# VauTRIOv1_0.net
KiCad netlist of a schematic drawn in EAGLE
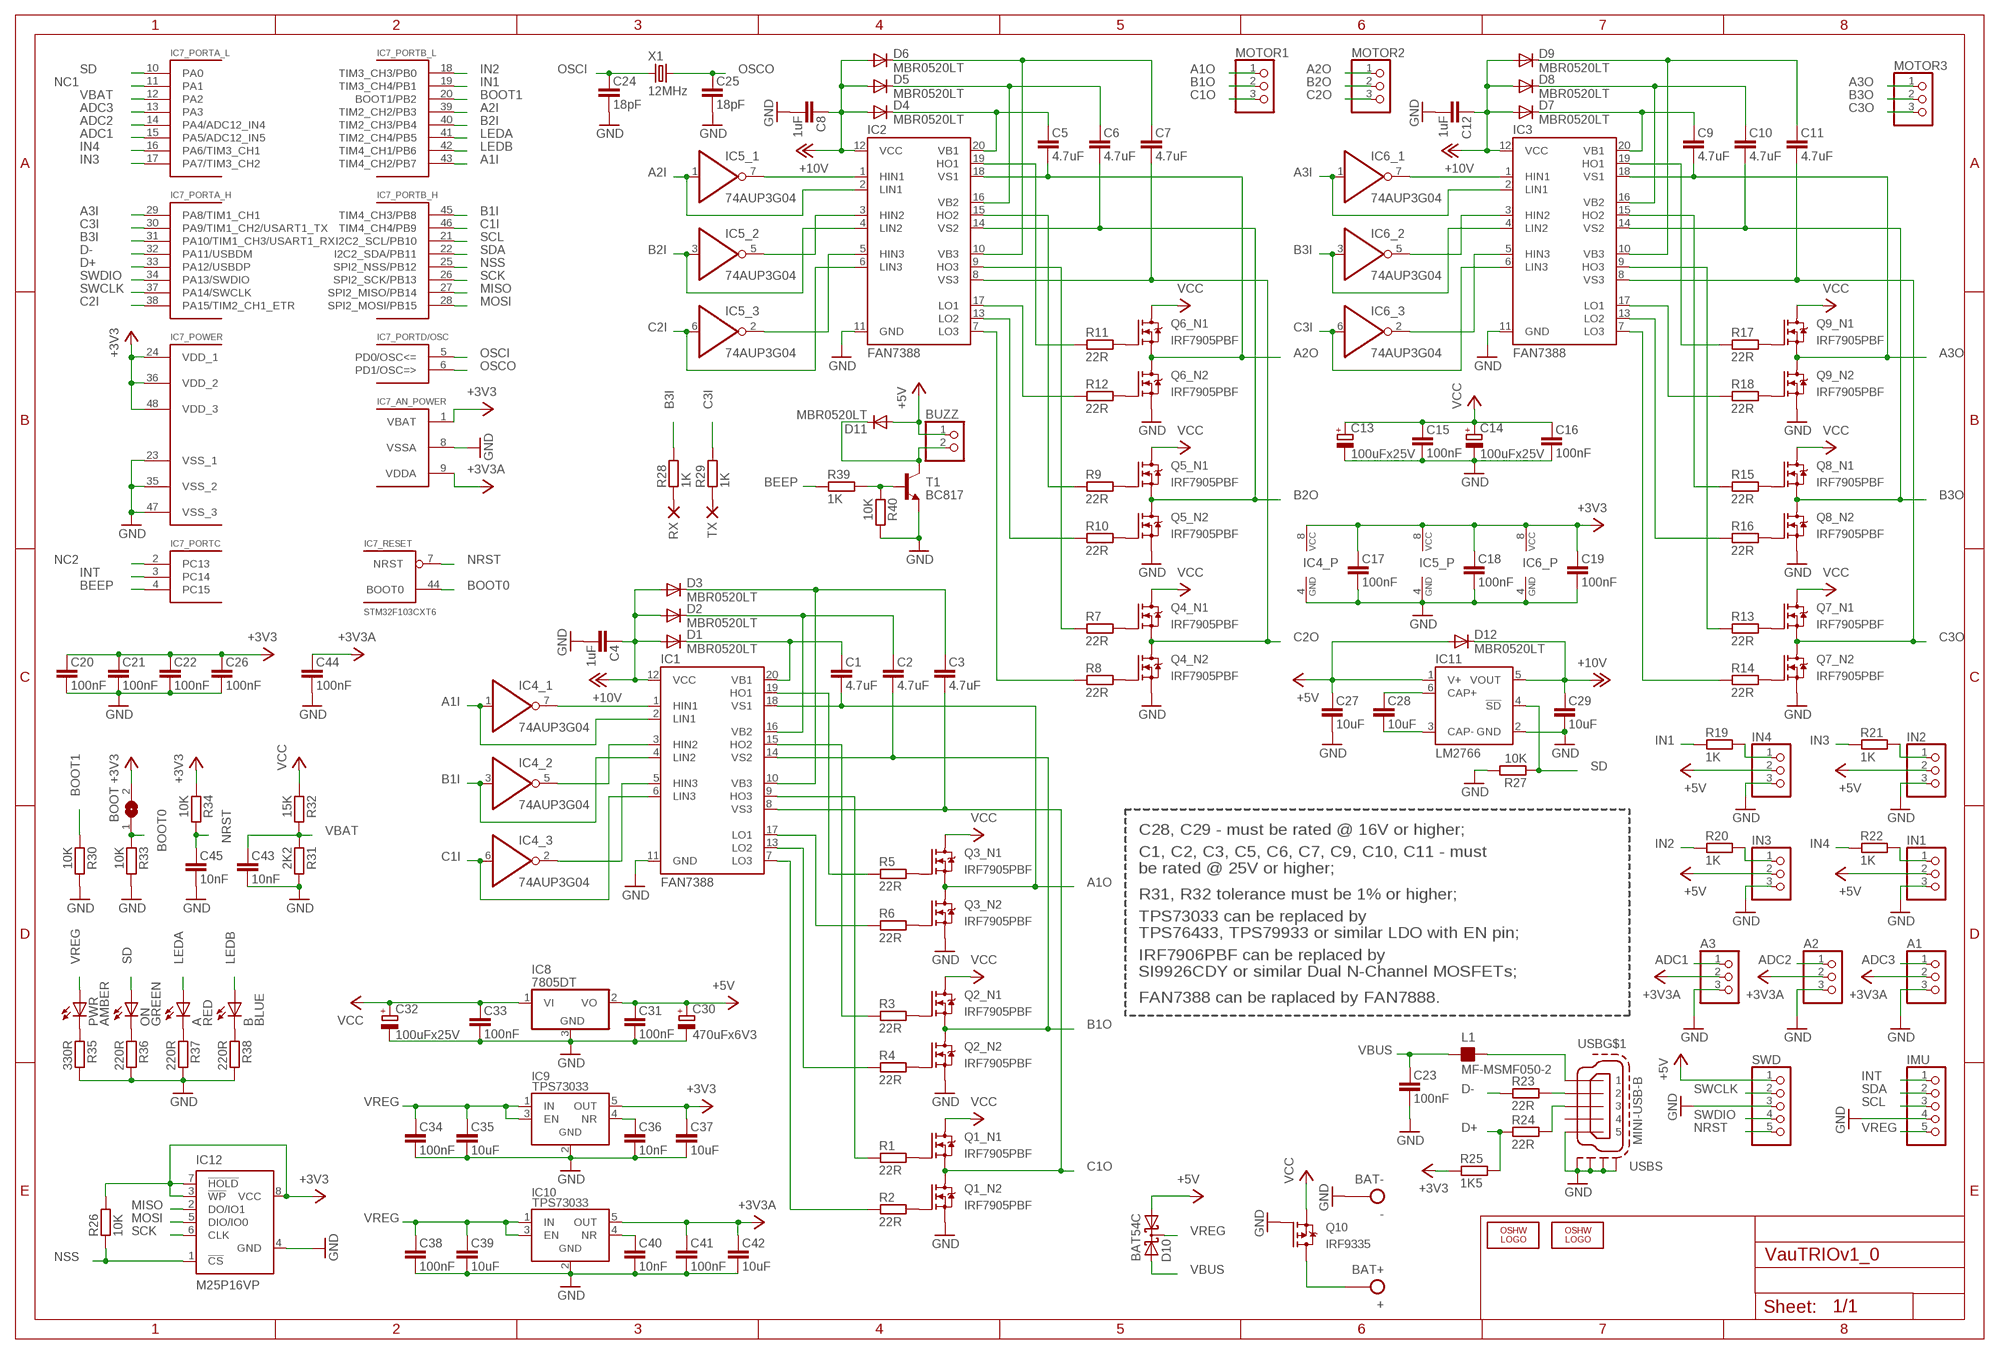
[diagram p0: schematic, sheet 1]

(export (version "E")
  (design (tool "Eeschema 10.0.6"))
  (components
    (comp (ref "+")
      (value "BAT+")
      (footprint "eagle-import:PAD20S")
      (libsource (lib "eagle-import") (part "POWER-PAD-20S"))
    )
    (comp (ref "-")
      (value "BAT-")
      (footprint "eagle-import:PAD20R")
      (libsource (lib "eagle-import") (part "POWER-PAD-20R"))
    )
    (comp (ref "A")
      (value "RED")
      (footprint "eagle-import:CHIPLED_0805")
      (libsource (lib "eagle-import") (part "LEDCHIPLED_0805"))
    )
    (comp (ref "A1")
      (value "PINHD-1X3")
      (footprint "eagle-import:1X03")
      (libsource (lib "eagle-import") (part "PINHD-1X3"))
    )
    (comp (ref "A2")
      (value "PINHD-1X3")
      (footprint "eagle-import:1X03")
      (libsource (lib "eagle-import") (part "PINHD-1X3"))
    )
    (comp (ref "A3")
      (value "PINHD-1X3")
      (footprint "eagle-import:1X03")
      (libsource (lib "eagle-import") (part "PINHD-1X3"))
    )
    (comp (ref "B")
      (value "BLUE")
      (footprint "eagle-import:CHIPLED_0805")
      (libsource (lib "eagle-import") (part "LEDCHIPLED_0805"))
    )
    (comp (ref "BOOT")
      (value "SJ")
      (footprint "eagle-import:SJ")
      (libsource (lib "eagle-import") (part "SJ"))
    )
    (comp (ref "BUZZ")
      (value "PINHD-1X2")
      (footprint "eagle-import:1X02")
      (libsource (lib "eagle-import") (part "PINHD-1X2"))
    )
    (comp (ref "C1")
      (value "4.7uF")
      (footprint "eagle-import:C0805")
      (libsource (lib "eagle-import") (part "C_EU_C0805"))
    )
    (comp (ref "C2")
      (value "4.7uF")
      (footprint "eagle-import:C0805")
      (libsource (lib "eagle-import") (part "C_EU_C0805"))
    )
    (comp (ref "C3")
      (value "4.7uF")
      (footprint "eagle-import:C0805")
      (libsource (lib "eagle-import") (part "C_EU_C0805"))
    )
    (comp (ref "C4")
      (value "1uF")
      (footprint "eagle-import:C0603G")
      (libsource (lib "eagle-import") (part "C_EU_C0603G"))
    )
    (comp (ref "C5")
      (value "4.7uF")
      (footprint "eagle-import:C0805")
      (libsource (lib "eagle-import") (part "C_EU_C0805"))
    )
    (comp (ref "C6")
      (value "4.7uF")
      (footprint "eagle-import:C0805")
      (libsource (lib "eagle-import") (part "C_EU_C0805"))
    )
    (comp (ref "C7")
      (value "4.7uF")
      (footprint "eagle-import:C0805")
      (libsource (lib "eagle-import") (part "C_EU_C0805"))
    )
    (comp (ref "C8")
      (value "1uF")
      (footprint "eagle-import:C0603G")
      (libsource (lib "eagle-import") (part "C_EU_C0603G"))
    )
    (comp (ref "C9")
      (value "4.7uF")
      (footprint "eagle-import:C0805")
      (libsource (lib "eagle-import") (part "C_EU_C0805"))
    )
    (comp (ref "C10")
      (value "4.7uF")
      (footprint "eagle-import:C0805")
      (libsource (lib "eagle-import") (part "C_EU_C0805"))
    )
    (comp (ref "C11")
      (value "4.7uF")
      (footprint "eagle-import:C0805")
      (libsource (lib "eagle-import") (part "C_EU_C0805"))
    )
    (comp (ref "C12")
      (value "1uF")
      (footprint "eagle-import:C0603G")
      (libsource (lib "eagle-import") (part "C_EU_C0603G"))
    )
    (comp (ref "C13")
      (value "100uFx25V")
      (footprint "eagle-import:E2,5-7")
      (libsource (lib "eagle-import") (part "CPOL-EUE2.5-7"))
    )
    (comp (ref "C14")
      (value "100uFx25V")
      (footprint "eagle-import:E2,5-7")
      (libsource (lib "eagle-import") (part "CPOL-EUE2.5-7"))
    )
    (comp (ref "C15")
      (value "100nF")
      (footprint "eagle-import:C0603G")
      (libsource (lib "eagle-import") (part "C_EU_C0603G"))
    )
    (comp (ref "C16")
      (value "100nF")
      (footprint "eagle-import:C0603G")
      (libsource (lib "eagle-import") (part "C_EU_C0603G"))
    )
    (comp (ref "C17")
      (value "100nF")
      (footprint "eagle-import:C0603G")
      (libsource (lib "eagle-import") (part "C_EU_C0603G"))
    )
    (comp (ref "C18")
      (value "100nF")
      (footprint "eagle-import:C0603G")
      (libsource (lib "eagle-import") (part "C_EU_C0603G"))
    )
    (comp (ref "C19")
      (value "100nF")
      (footprint "eagle-import:C0603G")
      (libsource (lib "eagle-import") (part "C_EU_C0603G"))
    )
    (comp (ref "C20")
      (value "100nF")
      (footprint "eagle-import:C0603G")
      (libsource (lib "eagle-import") (part "C_EU_C0603G"))
    )
    (comp (ref "C21")
      (value "100nF")
      (footprint "eagle-import:C0603G")
      (libsource (lib "eagle-import") (part "C_EU_C0603G"))
    )
    (comp (ref "C22")
      (value "100nF")
      (footprint "eagle-import:C0603G")
      (libsource (lib "eagle-import") (part "C_EU_C0603G"))
    )
    (comp (ref "C23")
      (value "100nF")
      (footprint "eagle-import:C0603G")
      (libsource (lib "eagle-import") (part "C_EU_C0603G"))
    )
    (comp (ref "C24")
      (value "18pF")
      (footprint "eagle-import:C0603G")
      (libsource (lib "eagle-import") (part "C_EU_C0603G"))
    )
    (comp (ref "C25")
      (value "18pF")
      (footprint "eagle-import:C0603G")
      (libsource (lib "eagle-import") (part "C_EU_C0603G"))
    )
    (comp (ref "C26")
      (value "100nF")
      (footprint "eagle-import:C0603G")
      (libsource (lib "eagle-import") (part "C_EU_C0603G"))
    )
    (comp (ref "C27")
      (value "10uF")
      (footprint "eagle-import:C0805G")
      (libsource (lib "eagle-import") (part "C_EU_C0805G"))
    )
    (comp (ref "C28")
      (value "10uF")
      (footprint "eagle-import:C0805")
      (libsource (lib "eagle-import") (part "C_EU_C0805"))
    )
    (comp (ref "C29")
      (value "10uF")
      (footprint "eagle-import:C0805G")
      (libsource (lib "eagle-import") (part "C_EU_C0805G"))
    )
    (comp (ref "C30")
      (value "470uFx6V3")
      (footprint "eagle-import:SMC_D")
      (libsource (lib "eagle-import") (part "CPOL-EUSMCD"))
    )
    (comp (ref "C31")
      (value "100nF")
      (footprint "eagle-import:C0603G")
      (libsource (lib "eagle-import") (part "C_EU_C0603G"))
    )
    (comp (ref "C32")
      (value "100uFx25V")
      (footprint "eagle-import:SMC_D")
      (libsource (lib "eagle-import") (part "CPOL-EUSMCD"))
    )
    (comp (ref "C33")
      (value "100nF")
      (footprint "eagle-import:C0603G")
      (libsource (lib "eagle-import") (part "C_EU_C0603G"))
    )
    (comp (ref "C34")
      (value "100nF")
      (footprint "eagle-import:C0603G")
      (libsource (lib "eagle-import") (part "C_EU_C0603G"))
    )
    (comp (ref "C35")
      (value "10uF")
      (footprint "eagle-import:C0805G")
      (libsource (lib "eagle-import") (part "C_EU_C0805G"))
    )
    (comp (ref "C36")
      (value "10nF")
      (footprint "eagle-import:C0603G")
      (libsource (lib "eagle-import") (part "C_EU_C0603G"))
    )
    (comp (ref "C37")
      (value "10uF")
      (footprint "eagle-import:C0805G")
      (libsource (lib "eagle-import") (part "C_EU_C0805G"))
    )
    (comp (ref "C38")
      (value "100nF")
      (footprint "eagle-import:C0603G")
      (libsource (lib "eagle-import") (part "C_EU_C0603G"))
    )
    (comp (ref "C39")
      (value "10uF")
      (footprint "eagle-import:C0805G")
      (libsource (lib "eagle-import") (part "C_EU_C0805G"))
    )
    (comp (ref "C40")
      (value "10nF")
      (footprint "eagle-import:C0603G")
      (libsource (lib "eagle-import") (part "C_EU_C0603G"))
    )
    (comp (ref "C41")
      (value "100nF")
      (footprint "eagle-import:C0603G")
      (libsource (lib "eagle-import") (part "C_EU_C0603G"))
    )
    (comp (ref "C42")
      (value "10uF")
      (footprint "eagle-import:C0805G")
      (libsource (lib "eagle-import") (part "C_EU_C0805G"))
    )
    (comp (ref "C43")
      (value "10nF")
      (footprint "eagle-import:C0603G")
      (libsource (lib "eagle-import") (part "C_EU_C0603G"))
    )
    (comp (ref "C44")
      (value "100nF")
      (footprint "eagle-import:C0603G")
      (libsource (lib "eagle-import") (part "C_EU_C0603G"))
    )
    (comp (ref "C45")
      (value "10nF")
      (footprint "eagle-import:C0603G")
      (libsource (lib "eagle-import") (part "C_EU_C0603G"))
    )
    (comp (ref "D1")
      (value "MBR0520LT")
      (footprint "eagle-import:SOD123")
      (libsource (lib "eagle-import") (part "MBR0520LT"))
    )
    (comp (ref "D2")
      (value "MBR0520LT")
      (footprint "eagle-import:SOD123")
      (libsource (lib "eagle-import") (part "MBR0520LT"))
    )
    (comp (ref "D3")
      (value "MBR0520LT")
      (footprint "eagle-import:SOD123")
      (libsource (lib "eagle-import") (part "MBR0520LT"))
    )
    (comp (ref "D4")
      (value "MBR0520LT")
      (footprint "eagle-import:SOD123")
      (libsource (lib "eagle-import") (part "MBR0520LT"))
    )
    (comp (ref "D5")
      (value "MBR0520LT")
      (footprint "eagle-import:SOD123")
      (libsource (lib "eagle-import") (part "MBR0520LT"))
    )
    (comp (ref "D6")
      (value "MBR0520LT")
      (footprint "eagle-import:SOD123")
      (libsource (lib "eagle-import") (part "MBR0520LT"))
    )
    (comp (ref "D7")
      (value "MBR0520LT")
      (footprint "eagle-import:SOD123")
      (libsource (lib "eagle-import") (part "MBR0520LT"))
    )
    (comp (ref "D8")
      (value "MBR0520LT")
      (footprint "eagle-import:SOD123")
      (libsource (lib "eagle-import") (part "MBR0520LT"))
    )
    (comp (ref "D9")
      (value "MBR0520LT")
      (footprint "eagle-import:SOD123")
      (libsource (lib "eagle-import") (part "MBR0520LT"))
    )
    (comp (ref "D10")
      (value "BAT54C")
      (footprint "eagle-import:SOT23")
      (libsource (lib "eagle-import") (part "BAT54C"))
    )
    (comp (ref "D11")
      (value "MBR0520LT")
      (footprint "eagle-import:SOD123")
      (libsource (lib "eagle-import") (part "MBR0520LT"))
    )
    (comp (ref "D12")
      (value "MBR0520LT")
      (footprint "eagle-import:SOD123")
      (libsource (lib "eagle-import") (part "MBR0520LT"))
    )
    (comp (ref "IC1")
      (value "FAN7388")
      (footprint "eagle-import:SOIC-20")
      (libsource (lib "eagle-import") (part "FAN7388"))
    )
    (comp (ref "IC2")
      (value "FAN7388")
      (footprint "eagle-import:SOIC-20")
      (libsource (lib "eagle-import") (part "FAN7388"))
    )
    (comp (ref "IC3")
      (value "FAN7388")
      (footprint "eagle-import:SOIC-20")
      (libsource (lib "eagle-import") (part "FAN7388"))
    )
    (comp (ref "IC4")
      (value "74AUP3G04")
      (footprint "eagle-import:R-PDSO-G8")
      (libsource (lib "eagle-import") (part "743G04AUP"))
    )
    (comp (ref "IC5")
      (value "74AUP3G04")
      (footprint "eagle-import:R-PDSO-G8")
      (libsource (lib "eagle-import") (part "743G04AUP"))
    )
    (comp (ref "IC6")
      (value "74AUP3G04")
      (footprint "eagle-import:R-PDSO-G8")
      (libsource (lib "eagle-import") (part "743G04AUP"))
    )
    (comp (ref "IC7")
      (value "STM32F103CXT6")
      (footprint "eagle-import:LQFP48")
      (libsource (lib "eagle-import") (part "STM32F103CXT6"))
    )
    (comp (ref "IC8")
      (value "7805DT")
      (footprint "eagle-import:TO252")
      (libsource (lib "eagle-import") (part "78DT05"))
    )
    (comp (ref "IC9")
      (value "TPS73033")
      (footprint "eagle-import:SOT23-5")
      (libsource (lib "eagle-import") (part "TPS769XX"))
    )
    (comp (ref "IC10")
      (value "TPS73033")
      (footprint "eagle-import:SOT23-5")
      (libsource (lib "eagle-import") (part "TPS769XX"))
    )
    (comp (ref "IC11")
      (value "LM2766")
      (footprint "eagle-import:SOT23-6")
      (libsource (lib "eagle-import") (part "LM2766"))
    )
    (comp (ref "IC12")
      (value "M25P16VP")
      (footprint "eagle-import:SOIC-8")
      (libsource (lib "eagle-import") (part "W25X40BVSNIG"))
    )
    (comp (ref "IMU")
      (value "PINHD-1X5")
      (footprint "eagle-import:1X05")
      (libsource (lib "eagle-import") (part "PINHD-1X5"))
    )
    (comp (ref "IN1")
      (value "PINHD-1X3")
      (footprint "eagle-import:1X03")
      (libsource (lib "eagle-import") (part "PINHD-1X3"))
    )
    (comp (ref "IN2")
      (value "PINHD-1X3")
      (footprint "eagle-import:1X03")
      (libsource (lib "eagle-import") (part "PINHD-1X3"))
    )
    (comp (ref "IN3")
      (value "PINHD-1X3")
      (footprint "eagle-import:1X03")
      (libsource (lib "eagle-import") (part "PINHD-1X3"))
    )
    (comp (ref "IN4")
      (value "PINHD-1X3")
      (footprint "eagle-import:1X03")
      (libsource (lib "eagle-import") (part "PINHD-1X3"))
    )
    (comp (ref "L1")
      (value "MF-MSMF050-2")
      (footprint "eagle-import:L0603")
      (libsource (lib "eagle-import") (part "FB_0603"))
    )
    (comp (ref "LOGO1")
      (value "OSHW_LOGO_10MILX0350-NT")
      (footprint "eagle-import:OSHW_10X350_NOTEXT")
      (libsource (lib "eagle-import") (part "OSHW_LOGO_10MILX0350-NT"))
    )
    (comp (ref "LOGO2")
      (value "OSHW_LOGO_FILLX0150-NT")
      (footprint "eagle-import:OSHW_FILLX150_NOTEXT")
      (libsource (lib "eagle-import") (part "OSHW_LOGO_FILLX0150-NT"))
    )
    (comp (ref "MOTOR1")
      (value "PINHD-1X3MOT")
      (footprint "eagle-import:1X03M")
      (libsource (lib "eagle-import") (part "PINHD-1X3MOT"))
    )
    (comp (ref "MOTOR2")
      (value "PINHD-1X3MOT")
      (footprint "eagle-import:1X03M")
      (libsource (lib "eagle-import") (part "PINHD-1X3MOT"))
    )
    (comp (ref "MOTOR3")
      (value "PINHD-1X3MOT")
      (footprint "eagle-import:1X03M")
      (libsource (lib "eagle-import") (part "PINHD-1X3MOT"))
    )
    (comp (ref "ON")
      (value "GREEN")
      (footprint "eagle-import:CHIPLED_0805")
      (libsource (lib "eagle-import") (part "LEDCHIPLED_0805"))
    )
    (comp (ref "PWR")
      (value "AMBER")
      (footprint "eagle-import:CHIPLED_0805")
      (libsource (lib "eagle-import") (part "LEDCHIPLED_0805"))
    )
    (comp (ref "Q1")
      (value "IRF7905PBF")
      (footprint "eagle-import:SOIC-8")
      (libsource (lib "eagle-import") (part "IRF7905PBF"))
    )
    (comp (ref "Q2")
      (value "IRF7905PBF")
      (footprint "eagle-import:SOIC-8")
      (libsource (lib "eagle-import") (part "IRF7905PBF"))
    )
    (comp (ref "Q3")
      (value "IRF7905PBF")
      (footprint "eagle-import:SOIC-8")
      (libsource (lib "eagle-import") (part "IRF7905PBF"))
    )
    (comp (ref "Q4")
      (value "IRF7905PBF")
      (footprint "eagle-import:SOIC-8")
      (libsource (lib "eagle-import") (part "IRF7905PBF"))
    )
    (comp (ref "Q5")
      (value "IRF7905PBF")
      (footprint "eagle-import:SOIC-8")
      (libsource (lib "eagle-import") (part "IRF7905PBF"))
    )
    (comp (ref "Q6")
      (value "IRF7905PBF")
      (footprint "eagle-import:SOIC-8")
      (libsource (lib "eagle-import") (part "IRF7905PBF"))
    )
    (comp (ref "Q7")
      (value "IRF7905PBF")
      (footprint "eagle-import:SOIC-8")
      (libsource (lib "eagle-import") (part "IRF7905PBF"))
    )
    (comp (ref "Q8")
      (value "IRF7905PBF")
      (footprint "eagle-import:SOIC-8")
      (libsource (lib "eagle-import") (part "IRF7905PBF"))
    )
    (comp (ref "Q9")
      (value "IRF7905PBF")
      (footprint "eagle-import:SOIC-8")
      (libsource (lib "eagle-import") (part "IRF7905PBF"))
    )
    (comp (ref "Q10")
      (value "IRF9335")
      (footprint "eagle-import:SOIC-8")
      (libsource (lib "eagle-import") (part "IRF9335"))
    )
    (comp (ref "R1")
      (value "22R")
      (footprint "eagle-import:R0603")
      (libsource (lib "eagle-import") (part "R_EU_R0603"))
    )
    (comp (ref "R2")
      (value "22R")
      (footprint "eagle-import:R0603")
      (libsource (lib "eagle-import") (part "R_EU_R0603"))
    )
    (comp (ref "R3")
      (value "22R")
      (footprint "eagle-import:R0603")
      (libsource (lib "eagle-import") (part "R_EU_R0603"))
    )
    (comp (ref "R4")
      (value "22R")
      (footprint "eagle-import:R0603")
      (libsource (lib "eagle-import") (part "R_EU_R0603"))
    )
    (comp (ref "R5")
      (value "22R")
      (footprint "eagle-import:R0603")
      (libsource (lib "eagle-import") (part "R_EU_R0603"))
    )
    (comp (ref "R6")
      (value "22R")
      (footprint "eagle-import:R0603")
      (libsource (lib "eagle-import") (part "R_EU_R0603"))
    )
    (comp (ref "R7")
      (value "22R")
      (footprint "eagle-import:R0603")
      (libsource (lib "eagle-import") (part "R_EU_R0603"))
    )
    (comp (ref "R8")
      (value "22R")
      (footprint "eagle-import:R0603")
      (libsource (lib "eagle-import") (part "R_EU_R0603"))
    )
    (comp (ref "R9")
      (value "22R")
      (footprint "eagle-import:R0603")
      (libsource (lib "eagle-import") (part "R_EU_R0603"))
    )
    (comp (ref "R10")
      (value "22R")
      (footprint "eagle-import:R0603")
      (libsource (lib "eagle-import") (part "R_EU_R0603"))
    )
    (comp (ref "R11")
      (value "22R")
      (footprint "eagle-import:R0603")
      (libsource (lib "eagle-import") (part "R_EU_R0603"))
    )
    (comp (ref "R12")
      (value "22R")
      (footprint "eagle-import:R0603")
      (libsource (lib "eagle-import") (part "R_EU_R0603"))
    )
    (comp (ref "R13")
      (value "22R")
      (footprint "eagle-import:R0603")
      (libsource (lib "eagle-import") (part "R_EU_R0603"))
    )
    (comp (ref "R14")
      (value "22R")
      (footprint "eagle-import:R0603")
      (libsource (lib "eagle-import") (part "R_EU_R0603"))
    )
    (comp (ref "R15")
      (value "22R")
      (footprint "eagle-import:R0603")
      (libsource (lib "eagle-import") (part "R_EU_R0603"))
    )
    (comp (ref "R16")
      (value "22R")
      (footprint "eagle-import:R0603")
      (libsource (lib "eagle-import") (part "R_EU_R0603"))
    )
    (comp (ref "R17")
      (value "22R")
      (footprint "eagle-import:R0603")
      (libsource (lib "eagle-import") (part "R_EU_R0603"))
    )
    (comp (ref "R18")
      (value "22R")
      (footprint "eagle-import:R0603")
      (libsource (lib "eagle-import") (part "R_EU_R0603"))
    )
    (comp (ref "R19")
      (value "1K")
      (footprint "eagle-import:R0603")
      (libsource (lib "eagle-import") (part "R_EU_R0603"))
    )
    (comp (ref "R20")
      (value "1K")
      (footprint "eagle-import:R0603")
      (libsource (lib "eagle-import") (part "R_EU_R0603"))
    )
    (comp (ref "R21")
      (value "1K")
      (footprint "eagle-import:R0603")
      (libsource (lib "eagle-import") (part "R_EU_R0603"))
    )
    (comp (ref "R22")
      (value "1K")
      (footprint "eagle-import:R0603")
      (libsource (lib "eagle-import") (part "R_EU_R0603"))
    )
    (comp (ref "R23")
      (value "22R")
      (footprint "eagle-import:R0603")
      (libsource (lib "eagle-import") (part "R_EU_R0603"))
    )
    (comp (ref "R24")
      (value "22R")
      (footprint "eagle-import:R0603")
      (libsource (lib "eagle-import") (part "R_EU_R0603"))
    )
    (comp (ref "R25")
      (value "1K5")
      (footprint "eagle-import:R0603")
      (libsource (lib "eagle-import") (part "R_EU_R0603"))
    )
    (comp (ref "R26")
      (value "10K")
      (footprint "eagle-import:R0603")
      (libsource (lib "eagle-import") (part "R_EU_R0603"))
    )
    (comp (ref "R27")
      (value "10K")
      (footprint "eagle-import:R0603G")
      (libsource (lib "eagle-import") (part "R_EU_R0603G"))
    )
    (comp (ref "R28")
      (value "1K")
      (footprint "eagle-import:R0603")
      (libsource (lib "eagle-import") (part "R_EU_R0603"))
    )
    (comp (ref "R29")
      (value "1K")
      (footprint "eagle-import:R0603")
      (libsource (lib "eagle-import") (part "R_EU_R0603"))
    )
    (comp (ref "R30")
      (value "10K")
      (footprint "eagle-import:R0603G")
      (libsource (lib "eagle-import") (part "R_EU_R0603G"))
    )
    (comp (ref "R31")
      (value "2K2")
      (footprint "eagle-import:R0603G")
      (libsource (lib "eagle-import") (part "R_EU_R0603G"))
    )
    (comp (ref "R32")
      (value "15K")
      (footprint "eagle-import:R0603")
      (libsource (lib "eagle-import") (part "R_EU_R0603"))
    )
    (comp (ref "R33")
      (value "10K")
      (footprint "eagle-import:R0603G")
      (libsource (lib "eagle-import") (part "R_EU_R0603G"))
    )
    (comp (ref "R34")
      (value "10K")
      (footprint "eagle-import:R0603")
      (libsource (lib "eagle-import") (part "R_EU_R0603"))
    )
    (comp (ref "R35")
      (value "330R")
      (footprint "eagle-import:R0603G")
      (libsource (lib "eagle-import") (part "R_EU_R0603G"))
    )
    (comp (ref "R36")
      (value "220R")
      (footprint "eagle-import:R0603G")
      (libsource (lib "eagle-import") (part "R_EU_R0603G"))
    )
    (comp (ref "R37")
      (value "220R")
      (footprint "eagle-import:R0603G")
      (libsource (lib "eagle-import") (part "R_EU_R0603G"))
    )
    (comp (ref "R38")
      (value "220R")
      (footprint "eagle-import:R0603G")
      (libsource (lib "eagle-import") (part "R_EU_R0603G"))
    )
    (comp (ref "R39")
      (value "1K")
      (footprint "eagle-import:R0603")
      (libsource (lib "eagle-import") (part "R_EU_R0603"))
    )
    (comp (ref "R40")
      (value "10K")
      (footprint "eagle-import:R0603G")
      (libsource (lib "eagle-import") (part "R_EU_R0603G"))
    )
    (comp (ref "RX")
      (value "PAD-SMD10R")
      (footprint "eagle-import:SMD10R")
      (libsource (lib "eagle-import") (part "PAD-SMD10R"))
    )
    (comp (ref "SWD")
      (value "PINHD-1X5")
      (footprint "eagle-import:1X05")
      (libsource (lib "eagle-import") (part "PINHD-1X5"))
    )
    (comp (ref "T1")
      (value "BC817")
      (footprint "eagle-import:SOT23-BEC")
      (libsource (lib "eagle-import") (part "BC817SMD-16LT1"))
    )
    (comp (ref "TX")
      (value "PAD-SMD10R")
      (footprint "eagle-import:SMD10R")
      (libsource (lib "eagle-import") (part "PAD-SMD10R"))
    )
    (comp (ref "USB")
      (value "MINI-USB-B")
      (footprint "eagle-import:32005-201")
      (libsource (lib "eagle-import") (part "MINI-USB-SCHIELD-32005-201"))
    )
    (comp (ref "X1")
      (value "12MHz")
      (footprint "eagle-import:HC49_S")
      (libsource (lib "eagle-import") (part "CRYSTALHC49S"))
    )
  )
  (nets
    (net (code "1") (name "+3V3") (class "Default")
      (node (ref "BOOT") (pin "2") (pinfunction "2_2") (pintype "passive"))
      (node (ref "C17") (pin "1") (pinfunction "1_1") (pintype "passive"))
      (node (ref "C18") (pin "1") (pinfunction "1_1") (pintype "passive"))
      (node (ref "C19") (pin "1") (pinfunction "1_1") (pintype "passive"))
      (node (ref "C20") (pin "1") (pinfunction "1_1") (pintype "passive"))
      (node (ref "C21") (pin "1") (pinfunction "1_1") (pintype "passive"))
      (node (ref "C22") (pin "1") (pinfunction "1_1") (pintype "passive"))
      (node (ref "C26") (pin "1") (pinfunction "1_1") (pintype "passive"))
      (node (ref "C37") (pin "1") (pinfunction "1_1") (pintype "passive"))
      (node (ref "IC12") (pin "3") (pinfunction "~{WP}_3") (pintype "input"))
      (node (ref "IC12") (pin "7") (pinfunction "~{HOLD}_7") (pintype "input"))
      (node (ref "IC12") (pin "8") (pinfunction "VCC_8") (pintype "power_in"))
      (node (ref "IC4") (pin "8") (pinfunction "VCC_8") (pintype "power_in"))
      (node (ref "IC5") (pin "8") (pinfunction "VCC_8") (pintype "power_in"))
      (node (ref "IC6") (pin "8") (pinfunction "VCC_8") (pintype "power_in"))
      (node (ref "IC7") (pin "1") (pinfunction "VBAT_1") (pintype "power_in"))
      (node (ref "IC7") (pin "24") (pinfunction "VDD_1_24") (pintype "power_in"))
      (node (ref "IC7") (pin "36") (pinfunction "VDD_2_36") (pintype "power_in"))
      (node (ref "IC7") (pin "48") (pinfunction "VDD_3_48") (pintype "power_in"))
      (node (ref "IC9") (pin "5") (pinfunction "OUT_5") (pintype "power_in"))
      (node (ref "R25") (pin "1") (pinfunction "1_1") (pintype "passive"))
      (node (ref "R26") (pin "2") (pinfunction "2_2") (pintype "passive"))
      (node (ref "R34") (pin "1") (pinfunction "1_1") (pintype "passive"))
    )
    (net (code "2") (name "+3V3A") (class "Default")
      (node (ref "A1") (pin "2") (pinfunction "2_2") (pintype "passive"))
      (node (ref "A2") (pin "2") (pinfunction "2_2") (pintype "passive"))
      (node (ref "A3") (pin "2") (pinfunction "2_2") (pintype "passive"))
      (node (ref "C41") (pin "1") (pinfunction "1_1") (pintype "passive"))
      (node (ref "C42") (pin "1") (pinfunction "1_1") (pintype "passive"))
      (node (ref "C44") (pin "1") (pinfunction "1_1") (pintype "passive"))
      (node (ref "IC10") (pin "5") (pinfunction "OUT_5") (pintype "power_in"))
      (node (ref "IC7") (pin "9") (pinfunction "VDDA_9") (pintype "power_in"))
    )
    (net (code "3") (name "+5V") (class "Default")
      (node (ref "BUZZ") (pin "1") (pinfunction "1_1") (pintype "passive"))
      (node (ref "C27") (pin "1") (pinfunction "1_1") (pintype "passive"))
      (node (ref "C30") (pin "+") (pinfunction "+_+") (pintype "passive"))
      (node (ref "C31") (pin "1") (pinfunction "1_1") (pintype "passive"))
      (node (ref "D10") (pin "1") (pinfunction "A1_1") (pintype "passive"))
      (node (ref "D11") (pin "A") (pinfunction "A_A") (pintype "passive"))
      (node (ref "D12") (pin "A") (pinfunction "A_A") (pintype "passive"))
      (node (ref "IC11") (pin "1") (pinfunction "V+_1") (pintype "input"))
      (node (ref "IC8") (pin "2") (pinfunction "VO_2") (pintype "passive"))
      (node (ref "IN1") (pin "2") (pinfunction "2_2") (pintype "passive"))
      (node (ref "IN2") (pin "2") (pinfunction "2_2") (pintype "passive"))
      (node (ref "IN3") (pin "2") (pinfunction "2_2") (pintype "passive"))
      (node (ref "IN4") (pin "2") (pinfunction "2_2") (pintype "passive"))
      (node (ref "SWD") (pin "1") (pinfunction "1_1") (pintype "passive"))
    )
    (net (code "4") (name "+10V") (class "Default")
      (node (ref "C12") (pin "1") (pinfunction "1_1") (pintype "passive"))
      (node (ref "C29") (pin "1") (pinfunction "1_1") (pintype "passive"))
      (node (ref "C4") (pin "1") (pinfunction "1_1") (pintype "passive"))
      (node (ref "C8") (pin "1") (pinfunction "1_1") (pintype "passive"))
      (node (ref "D1") (pin "A") (pinfunction "A_A") (pintype "passive"))
      (node (ref "D12") (pin "C") (pinfunction "C_C") (pintype "passive"))
      (node (ref "D2") (pin "A") (pinfunction "A_A") (pintype "passive"))
      (node (ref "D3") (pin "A") (pinfunction "A_A") (pintype "passive"))
      (node (ref "D4") (pin "A") (pinfunction "A_A") (pintype "passive"))
      (node (ref "D5") (pin "A") (pinfunction "A_A") (pintype "passive"))
      (node (ref "D6") (pin "A") (pinfunction "A_A") (pintype "passive"))
      (node (ref "D7") (pin "A") (pinfunction "A_A") (pintype "passive"))
      (node (ref "D8") (pin "A") (pinfunction "A_A") (pintype "passive"))
      (node (ref "D9") (pin "A") (pinfunction "A_A") (pintype "passive"))
      (node (ref "IC1") (pin "12") (pinfunction "VCC_12") (pintype "input"))
      (node (ref "IC11") (pin "5") (pinfunction "VOUT_5") (pintype "output"))
      (node (ref "IC2") (pin "12") (pinfunction "VCC_12") (pintype "input"))
      (node (ref "IC3") (pin "12") (pinfunction "VCC_12") (pintype "input"))
    )
    (net (code "5") (name "/A1I") (class "Default")
      (node (ref "IC1") (pin "2") (pinfunction "LIN1_2") (pintype "input"))
      (node (ref "IC4") (pin "1") (pinfunction "A_1") (pintype "input"))
      (node (ref "IC7") (pin "43") (pinfunction "TIM4_CH2/PB7_43") (pintype "bidirectional"))
    )
    (net (code "6") (name "/A1O") (class "Default")
      (node (ref "C1") (pin "2") (pinfunction "2_2") (pintype "passive"))
      (node (ref "IC1") (pin "18") (pinfunction "VS1_18") (pintype "input"))
      (node (ref "MOTOR1") (pin "1") (pinfunction "1_1") (pintype "passive"))
      (node (ref "Q3") (pin "3") (pinfunction "N-S_3") (pintype "passive"))
      (node (ref "Q3") (pin "7") (pinfunction "N-D_7") (pintype "passive"))
      (node (ref "Q3") (pin "8") (pinfunction "N-D_8") (pintype "passive"))
    )
    (net (code "7") (name "/A2I") (class "Default")
      (node (ref "IC2") (pin "2") (pinfunction "LIN1_2") (pintype "input"))
      (node (ref "IC5") (pin "1") (pinfunction "A_1") (pintype "input"))
      (node (ref "IC7") (pin "39") (pinfunction "TIM2_CH2/PB3_39") (pintype "bidirectional"))
    )
    (net (code "8") (name "/A2O") (class "Default")
      (node (ref "C5") (pin "2") (pinfunction "2_2") (pintype "passive"))
      (node (ref "IC2") (pin "18") (pinfunction "VS1_18") (pintype "input"))
      (node (ref "MOTOR2") (pin "1") (pinfunction "1_1") (pintype "passive"))
      (node (ref "Q6") (pin "3") (pinfunction "N-S_3") (pintype "passive"))
      (node (ref "Q6") (pin "7") (pinfunction "N-D_7") (pintype "passive"))
      (node (ref "Q6") (pin "8") (pinfunction "N-D_8") (pintype "passive"))
    )
    (net (code "9") (name "/A3I") (class "Default")
      (node (ref "IC3") (pin "2") (pinfunction "LIN1_2") (pintype "input"))
      (node (ref "IC6") (pin "1") (pinfunction "A_1") (pintype "input"))
      (node (ref "IC7") (pin "29") (pinfunction "PA8/TIM1_CH1_29") (pintype "bidirectional"))
    )
    (net (code "10") (name "/A3O") (class "Default")
      (node (ref "C9") (pin "2") (pinfunction "2_2") (pintype "passive"))
      (node (ref "IC3") (pin "18") (pinfunction "VS1_18") (pintype "input"))
      (node (ref "MOTOR3") (pin "1") (pinfunction "1_1") (pintype "passive"))
      (node (ref "Q9") (pin "3") (pinfunction "N-S_3") (pintype "passive"))
      (node (ref "Q9") (pin "7") (pinfunction "N-D_7") (pintype "passive"))
      (node (ref "Q9") (pin "8") (pinfunction "N-D_8") (pintype "passive"))
    )
    (net (code "11") (name "/ADC1") (class "Default")
      (node (ref "A3") (pin "1") (pinfunction "1_1") (pintype "passive"))
      (node (ref "IC7") (pin "15") (pinfunction "PA5/ADC12_IN5_15") (pintype "bidirectional"))
    )
    (net (code "12") (name "/ADC2") (class "Default")
      (node (ref "A2") (pin "1") (pinfunction "1_1") (pintype "passive"))
      (node (ref "IC7") (pin "14") (pinfunction "PA4/ADC12_IN4_14") (pintype "bidirectional"))
    )
    (net (code "13") (name "/ADC3") (class "Default")
      (node (ref "A1") (pin "1") (pinfunction "1_1") (pintype "passive"))
      (node (ref "IC7") (pin "13") (pinfunction "PA3_13") (pintype "bidirectional"))
    )
    (net (code "14") (name "/B1I") (class "Default")
      (node (ref "IC1") (pin "4") (pinfunction "LIN2_4") (pintype "input"))
      (node (ref "IC4") (pin "3") (pinfunction "A_3") (pintype "input"))
      (node (ref "IC7") (pin "45") (pinfunction "TIM4_CH3/PB8_45") (pintype "bidirectional"))
    )
    (net (code "15") (name "/B1O") (class "Default")
      (node (ref "C2") (pin "2") (pinfunction "2_2") (pintype "passive"))
      (node (ref "IC1") (pin "14") (pinfunction "VS2_14") (pintype "input"))
      (node (ref "MOTOR1") (pin "2") (pinfunction "2_2") (pintype "passive"))
      (node (ref "Q2") (pin "3") (pinfunction "N-S_3") (pintype "passive"))
      (node (ref "Q2") (pin "7") (pinfunction "N-D_7") (pintype "passive"))
      (node (ref "Q2") (pin "8") (pinfunction "N-D_8") (pintype "passive"))
    )
    (net (code "16") (name "/B2I") (class "Default")
      (node (ref "IC2") (pin "4") (pinfunction "LIN2_4") (pintype "input"))
      (node (ref "IC5") (pin "3") (pinfunction "A_3") (pintype "input"))
      (node (ref "IC7") (pin "40") (pinfunction "TIM2_CH3/PB4_40") (pintype "bidirectional"))
    )
    (net (code "17") (name "/B2O") (class "Default")
      (node (ref "C6") (pin "2") (pinfunction "2_2") (pintype "passive"))
      (node (ref "IC2") (pin "14") (pinfunction "VS2_14") (pintype "input"))
      (node (ref "MOTOR2") (pin "2") (pinfunction "2_2") (pintype "passive"))
      (node (ref "Q5") (pin "3") (pinfunction "N-S_3") (pintype "passive"))
      (node (ref "Q5") (pin "7") (pinfunction "N-D_7") (pintype "passive"))
      (node (ref "Q5") (pin "8") (pinfunction "N-D_8") (pintype "passive"))
    )
    (net (code "18") (name "/B3I") (class "Default")
      (node (ref "IC3") (pin "4") (pinfunction "LIN2_4") (pintype "input"))
      (node (ref "IC6") (pin "3") (pinfunction "A_3") (pintype "input"))
      (node (ref "IC7") (pin "31") (pinfunction "PA10/TIM1_CH3/USART1_RX_31") (pintype "bidirectional"))
      (node (ref "R28") (pin "2") (pinfunction "2_2") (pintype "passive"))
    )
    (net (code "19") (name "/B3O") (class "Default")
      (node (ref "C10") (pin "2") (pinfunction "2_2") (pintype "passive"))
      (node (ref "IC3") (pin "14") (pinfunction "VS2_14") (pintype "input"))
      (node (ref "MOTOR3") (pin "2") (pinfunction "2_2") (pintype "passive"))
      (node (ref "Q8") (pin "3") (pinfunction "N-S_3") (pintype "passive"))
      (node (ref "Q8") (pin "7") (pinfunction "N-D_7") (pintype "passive"))
      (node (ref "Q8") (pin "8") (pinfunction "N-D_8") (pintype "passive"))
    )
    (net (code "20") (name "/BEEP") (class "Default")
      (node (ref "IC7") (pin "4") (pinfunction "PC15_4") (pintype "bidirectional"))
      (node (ref "R39") (pin "1") (pinfunction "1_1") (pintype "passive"))
    )
    (net (code "21") (name "/BOOT0") (class "Default")
      (node (ref "BOOT") (pin "1") (pinfunction "1_1") (pintype "passive"))
      (node (ref "IC7") (pin "44") (pinfunction "BOOT0_44") (pintype "input"))
      (node (ref "R33") (pin "1") (pinfunction "1_1") (pintype "passive"))
    )
    (net (code "22") (name "/BOOT1") (class "Default")
      (node (ref "IC7") (pin "20") (pinfunction "BOOT1/PB2_20") (pintype "bidirectional"))
      (node (ref "R30") (pin "1") (pinfunction "1_1") (pintype "passive"))
    )
    (net (code "23") (name "/C1I") (class "Default")
      (node (ref "IC1") (pin "6") (pinfunction "LIN3_6") (pintype "input"))
      (node (ref "IC4") (pin "6") (pinfunction "A_6") (pintype "input"))
      (node (ref "IC7") (pin "46") (pinfunction "TIM4_CH4/PB9_46") (pintype "bidirectional"))
    )
    (net (code "24") (name "/C1O") (class "Default")
      (node (ref "C3") (pin "2") (pinfunction "2_2") (pintype "passive"))
      (node (ref "IC1") (pin "8") (pinfunction "VS3_8") (pintype "input"))
      (node (ref "MOTOR1") (pin "3") (pinfunction "3_3") (pintype "passive"))
      (node (ref "Q1") (pin "3") (pinfunction "N-S_3") (pintype "passive"))
      (node (ref "Q1") (pin "7") (pinfunction "N-D_7") (pintype "passive"))
      (node (ref "Q1") (pin "8") (pinfunction "N-D_8") (pintype "passive"))
    )
    (net (code "25") (name "/C2I") (class "Default")
      (node (ref "IC2") (pin "6") (pinfunction "LIN3_6") (pintype "input"))
      (node (ref "IC5") (pin "6") (pinfunction "A_6") (pintype "input"))
      (node (ref "IC7") (pin "38") (pinfunction "PA15/TIM2_CH1_ETR_38") (pintype "bidirectional"))
    )
    (net (code "26") (name "/C2O") (class "Default")
      (node (ref "C7") (pin "2") (pinfunction "2_2") (pintype "passive"))
      (node (ref "IC2") (pin "8") (pinfunction "VS3_8") (pintype "input"))
      (node (ref "MOTOR2") (pin "3") (pinfunction "3_3") (pintype "passive"))
      (node (ref "Q4") (pin "3") (pinfunction "N-S_3") (pintype "passive"))
      (node (ref "Q4") (pin "7") (pinfunction "N-D_7") (pintype "passive"))
      (node (ref "Q4") (pin "8") (pinfunction "N-D_8") (pintype "passive"))
    )
    (net (code "27") (name "/C3I") (class "Default")
      (node (ref "IC3") (pin "6") (pinfunction "LIN3_6") (pintype "input"))
      (node (ref "IC6") (pin "6") (pinfunction "A_6") (pintype "input"))
      (node (ref "IC7") (pin "30") (pinfunction "PA9/TIM1_CH2/USART1_TX_30") (pintype "bidirectional"))
      (node (ref "R29") (pin "2") (pinfunction "2_2") (pintype "passive"))
    )
    (net (code "28") (name "/C3O") (class "Default")
      (node (ref "C11") (pin "2") (pinfunction "2_2") (pintype "passive"))
      (node (ref "IC3") (pin "8") (pinfunction "VS3_8") (pintype "input"))
      (node (ref "MOTOR3") (pin "3") (pinfunction "3_3") (pintype "passive"))
      (node (ref "Q7") (pin "3") (pinfunction "N-S_3") (pintype "passive"))
      (node (ref "Q7") (pin "7") (pinfunction "N-D_7") (pintype "passive"))
      (node (ref "Q7") (pin "8") (pinfunction "N-D_8") (pintype "passive"))
    )
    (net (code "29") (name "/D+") (class "Default")
      (node (ref "IC7") (pin "33") (pinfunction "PA12/USBDP_33") (pintype "bidirectional"))
      (node (ref "R24") (pin "1") (pinfunction "1_1") (pintype "passive"))
      (node (ref "R25") (pin "2") (pinfunction "2_2") (pintype "passive"))
    )
    (net (code "30") (name "/D-") (class "Default")
      (node (ref "IC7") (pin "32") (pinfunction "PA11/USBDM_32") (pintype "bidirectional"))
      (node (ref "R23") (pin "1") (pinfunction "1_1") (pintype "passive"))
    )
    (net (code "31") (name "/IN1") (class "Default")
      (node (ref "IC7") (pin "19") (pinfunction "TIM3_CH4/PB1_19") (pintype "bidirectional"))
      (node (ref "R19") (pin "1") (pinfunction "1_1") (pintype "passive"))
    )
    (net (code "32") (name "/IN2") (class "Default")
      (node (ref "IC7") (pin "18") (pinfunction "TIM3_CH3/PB0_18") (pintype "bidirectional"))
      (node (ref "R20") (pin "1") (pinfunction "1_1") (pintype "passive"))
    )
    (net (code "33") (name "/IN3") (class "Default")
      (node (ref "IC7") (pin "17") (pinfunction "PA7/TIM3_CH2_17") (pintype "bidirectional"))
      (node (ref "R21") (pin "1") (pinfunction "1_1") (pintype "passive"))
    )
    (net (code "34") (name "/IN4") (class "Default")
      (node (ref "IC7") (pin "16") (pinfunction "PA6/TIM3_CH1_16") (pintype "bidirectional"))
      (node (ref "R22") (pin "1") (pinfunction "1_1") (pintype "passive"))
    )
    (net (code "35") (name "/INT") (class "Default")
      (node (ref "IC7") (pin "3") (pinfunction "PC14_3") (pintype "bidirectional"))
      (node (ref "IMU") (pin "1") (pinfunction "1_1") (pintype "passive"))
    )
    (net (code "36") (name "/LEDA") (class "Default")
      (node (ref "A") (pin "A") (pinfunction "A_A") (pintype "passive"))
      (node (ref "IC7") (pin "41") (pinfunction "TIM2_CH4/PB5_41") (pintype "bidirectional"))
    )
    (net (code "37") (name "/LEDB") (class "Default")
      (node (ref "B") (pin "A") (pinfunction "A_A") (pintype "passive"))
      (node (ref "IC7") (pin "42") (pinfunction "TIM4_CH1/PB6_42") (pintype "bidirectional"))
    )
    (net (code "38") (name "/MISO") (class "Default")
      (node (ref "IC12") (pin "2") (pinfunction "DO/IO1_2") (pintype "output"))
      (node (ref "IC7") (pin "27") (pinfunction "SPI2_MISO/PB14_27") (pintype "bidirectional"))
    )
    (net (code "39") (name "/MOSI") (class "Default")
      (node (ref "IC12") (pin "5") (pinfunction "DIO/IO0_5") (pintype "bidirectional"))
      (node (ref "IC7") (pin "28") (pinfunction "SPI2_MOSI/PB15_28") (pintype "bidirectional"))
    )
    (net (code "40") (name "/NC1") (class "Default")
      (node (ref "IC7") (pin "11") (pinfunction "PA1_11") (pintype "bidirectional"))
    )
    (net (code "41") (name "/NC2") (class "Default")
      (node (ref "IC7") (pin "2") (pinfunction "PC13_2") (pintype "bidirectional"))
    )
    (net (code "42") (name "/NRST") (class "Default")
      (node (ref "C45") (pin "1") (pinfunction "1_1") (pintype "passive"))
      (node (ref "IC7") (pin "7") (pinfunction "NRST_7") (pintype "input"))
      (node (ref "R34") (pin "2") (pinfunction "2_2") (pintype "passive"))
      (node (ref "SWD") (pin "5") (pinfunction "5_5") (pintype "passive"))
    )
    (net (code "43") (name "/NSS") (class "Default")
      (node (ref "IC12") (pin "1") (pinfunction "~{CS}_1") (pintype "input"))
      (node (ref "IC7") (pin "25") (pinfunction "SPI2_NSS/PB12_25") (pintype "bidirectional"))
      (node (ref "R26") (pin "1") (pinfunction "1_1") (pintype "passive"))
    )
    (net (code "44") (name "/OSCI") (class "Default")
      (node (ref "C24") (pin "1") (pinfunction "1_1") (pintype "passive"))
      (node (ref "IC7") (pin "5") (pinfunction "PD0/OSC<=_5") (pintype "bidirectional"))
      (node (ref "X1") (pin "1") (pinfunction "1_1") (pintype "passive"))
    )
    (net (code "45") (name "/OSCO") (class "Default")
      (node (ref "C25") (pin "1") (pinfunction "1_1") (pintype "passive"))
      (node (ref "IC7") (pin "6") (pinfunction "PD1/OSC=>_6") (pintype "bidirectional"))
      (node (ref "X1") (pin "2") (pinfunction "2_2") (pintype "passive"))
    )
    (net (code "46") (name "/SCK") (class "Default")
      (node (ref "IC12") (pin "6") (pinfunction "CLK_6") (pintype "input"))
      (node (ref "IC7") (pin "26") (pinfunction "SPI2_SCK/PB13_26") (pintype "bidirectional"))
    )
    (net (code "47") (name "/SCL") (class "Default")
      (node (ref "IC7") (pin "21") (pinfunction "I2C2_SCL/PB10_21") (pintype "bidirectional"))
      (node (ref "IMU") (pin "3") (pinfunction "3_3") (pintype "passive"))
    )
    (net (code "48") (name "/SD") (class "Default")
      (node (ref "IC11") (pin "4") (pinfunction "~{SD}_4") (pintype "input"))
      (node (ref "IC7") (pin "10") (pinfunction "PA0_10") (pintype "bidirectional"))
      (node (ref "ON") (pin "A") (pinfunction "A_A") (pintype "passive"))
      (node (ref "R27") (pin "1") (pinfunction "1_1") (pintype "passive"))
    )
    (net (code "49") (name "/SDA") (class "Default")
      (node (ref "IC7") (pin "22") (pinfunction "I2C2_SDA/PB11_22") (pintype "bidirectional"))
      (node (ref "IMU") (pin "2") (pinfunction "2_2") (pintype "passive"))
    )
    (net (code "50") (name "/SWCLK") (class "Default")
      (node (ref "IC7") (pin "37") (pinfunction "PA14/SWCLK_37") (pintype "bidirectional"))
      (node (ref "SWD") (pin "2") (pinfunction "2_2") (pintype "passive"))
    )
    (net (code "51") (name "/SWDIO") (class "Default")
      (node (ref "IC7") (pin "34") (pinfunction "PA13/SWDIO_34") (pintype "bidirectional"))
      (node (ref "SWD") (pin "4") (pinfunction "4_4") (pintype "passive"))
    )
    (net (code "52") (name "/VBAT") (class "Default")
      (node (ref "C43") (pin "1") (pinfunction "1_1") (pintype "passive"))
      (node (ref "IC7") (pin "12") (pinfunction "PA2_12") (pintype "bidirectional"))
      (node (ref "R31") (pin "1") (pinfunction "1_1") (pintype "passive"))
      (node (ref "R32") (pin "2") (pinfunction "2_2") (pintype "passive"))
    )
    (net (code "53") (name "/VBUS") (class "Default")
      (node (ref "C23") (pin "1") (pinfunction "1_1") (pintype "passive"))
      (node (ref "D10") (pin "2") (pinfunction "A2_2") (pintype "passive"))
      (node (ref "L1") (pin "1") (pinfunction "1_1") (pintype "passive"))
    )
    (net (code "54") (name "/VREG") (class "Default")
      (node (ref "C34") (pin "1") (pinfunction "1_1") (pintype "passive"))
      (node (ref "C35") (pin "1") (pinfunction "1_1") (pintype "passive"))
      (node (ref "C38") (pin "1") (pinfunction "1_1") (pintype "passive"))
      (node (ref "C39") (pin "1") (pinfunction "1_1") (pintype "passive"))
      (node (ref "D10") (pin "3") (pinfunction "CC_3") (pintype "passive"))
      (node (ref "IC10") (pin "1") (pinfunction "IN_1") (pintype "power_in"))
      (node (ref "IC10") (pin "3") (pinfunction "EN_3") (pintype "passive"))
      (node (ref "IC9") (pin "1") (pinfunction "IN_1") (pintype "power_in"))
      (node (ref "IC9") (pin "3") (pinfunction "EN_3") (pintype "passive"))
      (node (ref "IMU") (pin "5") (pinfunction "5_5") (pintype "passive"))
      (node (ref "PWR") (pin "A") (pinfunction "A_A") (pintype "passive"))
    )
    (net (code "55") (name "GND") (class "Default")
      (node (ref "-") (pin "P$1") (pinfunction "1_P$1") (pintype "bidirectional"))
      (node (ref "A1") (pin "3") (pinfunction "3_3") (pintype "passive"))
      (node (ref "A2") (pin "3") (pinfunction "3_3") (pintype "passive"))
      (node (ref "A3") (pin "3") (pinfunction "3_3") (pintype "passive"))
      (node (ref "C12") (pin "2") (pinfunction "2_2") (pintype "passive"))
      (node (ref "C13") (pin "-") (pinfunction "-_-") (pintype "passive"))
      (node (ref "C14") (pin "-") (pinfunction "-_-") (pintype "passive"))
      (node (ref "C15") (pin "2") (pinfunction "2_2") (pintype "passive"))
      (node (ref "C16") (pin "2") (pinfunction "2_2") (pintype "passive"))
      (node (ref "C17") (pin "2") (pinfunction "2_2") (pintype "passive"))
      (node (ref "C18") (pin "2") (pinfunction "2_2") (pintype "passive"))
      (node (ref "C19") (pin "2") (pinfunction "2_2") (pintype "passive"))
      (node (ref "C20") (pin "2") (pinfunction "2_2") (pintype "passive"))
      (node (ref "C21") (pin "2") (pinfunction "2_2") (pintype "passive"))
      (node (ref "C22") (pin "2") (pinfunction "2_2") (pintype "passive"))
      (node (ref "C23") (pin "2") (pinfunction "2_2") (pintype "passive"))
      (node (ref "C24") (pin "2") (pinfunction "2_2") (pintype "passive"))
      (node (ref "C25") (pin "2") (pinfunction "2_2") (pintype "passive"))
      (node (ref "C26") (pin "2") (pinfunction "2_2") (pintype "passive"))
      (node (ref "C27") (pin "2") (pinfunction "2_2") (pintype "passive"))
      (node (ref "C29") (pin "2") (pinfunction "2_2") (pintype "passive"))
      (node (ref "C30") (pin "-") (pinfunction "-_-") (pintype "passive"))
      (node (ref "C31") (pin "2") (pinfunction "2_2") (pintype "passive"))
      (node (ref "C32") (pin "-") (pinfunction "-_-") (pintype "passive"))
      (node (ref "C33") (pin "2") (pinfunction "2_2") (pintype "passive"))
      (node (ref "C34") (pin "2") (pinfunction "2_2") (pintype "passive"))
      (node (ref "C35") (pin "2") (pinfunction "2_2") (pintype "passive"))
      (node (ref "C36") (pin "2") (pinfunction "2_2") (pintype "passive"))
      (node (ref "C37") (pin "2") (pinfunction "2_2") (pintype "passive"))
      (node (ref "C38") (pin "2") (pinfunction "2_2") (pintype "passive"))
      (node (ref "C39") (pin "2") (pinfunction "2_2") (pintype "passive"))
      (node (ref "C4") (pin "2") (pinfunction "2_2") (pintype "passive"))
      (node (ref "C40") (pin "2") (pinfunction "2_2") (pintype "passive"))
      (node (ref "C41") (pin "2") (pinfunction "2_2") (pintype "passive"))
      (node (ref "C42") (pin "2") (pinfunction "2_2") (pintype "passive"))
      (node (ref "C43") (pin "2") (pinfunction "2_2") (pintype "passive"))
      (node (ref "C44") (pin "2") (pinfunction "2_2") (pintype "passive"))
      (node (ref "C45") (pin "2") (pinfunction "2_2") (pintype "passive"))
      (node (ref "C8") (pin "2") (pinfunction "2_2") (pintype "passive"))
      (node (ref "IC1") (pin "11") (pinfunction "GND_11") (pintype "power_in"))
      (node (ref "IC10") (pin "2") (pinfunction "GND_2") (pintype "power_in"))
      (node (ref "IC11") (pin "2") (pinfunction "GND_2") (pintype "power_in"))
      (node (ref "IC12") (pin "4") (pinfunction "GND_4") (pintype "power_in"))
      (node (ref "IC2") (pin "11") (pinfunction "GND_11") (pintype "power_in"))
      (node (ref "IC3") (pin "11") (pinfunction "GND_11") (pintype "power_in"))
      (node (ref "IC4") (pin "4") (pinfunction "GND_4") (pintype "power_in"))
      (node (ref "IC5") (pin "4") (pinfunction "GND_4") (pintype "power_in"))
      (node (ref "IC6") (pin "4") (pinfunction "GND_4") (pintype "power_in"))
      (node (ref "IC7") (pin "23") (pinfunction "VSS_1_23") (pintype "power_in"))
      (node (ref "IC7") (pin "35") (pinfunction "VSS_2_35") (pintype "power_in"))
      (node (ref "IC7") (pin "47") (pinfunction "VSS_3_47") (pintype "power_in"))
      (node (ref "IC7") (pin "8") (pinfunction "VSSA_8") (pintype "power_in"))
      (node (ref "IC8") (pin "3") (pinfunction "GND_3") (pintype "passive"))
      (node (ref "IC9") (pin "2") (pinfunction "GND_2") (pintype "power_in"))
      (node (ref "IMU") (pin "4") (pinfunction "4_4") (pintype "passive"))
      (node (ref "IN1") (pin "3") (pinfunction "3_3") (pintype "passive"))
      (node (ref "IN2") (pin "3") (pinfunction "3_3") (pintype "passive"))
      (node (ref "IN3") (pin "3") (pinfunction "3_3") (pintype "passive"))
      (node (ref "IN4") (pin "3") (pinfunction "3_3") (pintype "passive"))
      (node (ref "Q1") (pin "1") (pinfunction "N-S_1") (pintype "passive"))
      (node (ref "Q10") (pin "4") (pinfunction "P-G_4") (pintype "passive"))
      (node (ref "Q2") (pin "1") (pinfunction "N-S_1") (pintype "passive"))
      (node (ref "Q3") (pin "1") (pinfunction "N-S_1") (pintype "passive"))
      (node (ref "Q4") (pin "1") (pinfunction "N-S_1") (pintype "passive"))
      (node (ref "Q5") (pin "1") (pinfunction "N-S_1") (pintype "passive"))
      (node (ref "Q6") (pin "1") (pinfunction "N-S_1") (pintype "passive"))
      (node (ref "Q7") (pin "1") (pinfunction "N-S_1") (pintype "passive"))
      (node (ref "Q8") (pin "1") (pinfunction "N-S_1") (pintype "passive"))
      (node (ref "Q9") (pin "1") (pinfunction "N-S_1") (pintype "passive"))
      (node (ref "R27") (pin "2") (pinfunction "2_2") (pintype "passive"))
      (node (ref "R30") (pin "2") (pinfunction "2_2") (pintype "passive"))
      (node (ref "R31") (pin "2") (pinfunction "2_2") (pintype "passive"))
      (node (ref "R33") (pin "2") (pinfunction "2_2") (pintype "passive"))
      (node (ref "R35") (pin "2") (pinfunction "2_2") (pintype "passive"))
      (node (ref "R36") (pin "2") (pinfunction "2_2") (pintype "passive"))
      (node (ref "R37") (pin "2") (pinfunction "2_2") (pintype "passive"))
      (node (ref "R38") (pin "2") (pinfunction "2_2") (pintype "passive"))
      (node (ref "R40") (pin "2") (pinfunction "2_2") (pintype "passive"))
      (node (ref "SWD") (pin "3") (pinfunction "3_3") (pintype "passive"))
      (node (ref "T1") (pin "E") (pinfunction "E_E") (pintype "passive"))
      (node (ref "USB") (pin "5") (pinfunction "5_5") (pintype "passive"))
      (node (ref "USB") (pin "M1") (pinfunction "S1_M1") (pintype "passive"))
      (node (ref "USB") (pin "M2") (pinfunction "S2_M2") (pintype "passive"))
      (node (ref "USB") (pin "M3") (pinfunction "S3_M3") (pintype "passive"))
      (node (ref "USB") (pin "M4") (pinfunction "S4_M4") (pintype "passive"))
    )
    (net (code "56") (name "Net-(+-1)") (class "Default")
      (node (ref "+") (pin "P$1") (pinfunction "1_P$1") (pintype "bidirectional"))
      (node (ref "Q10") (pin "5") (pinfunction "P-D_5") (pintype "passive"))
      (node (ref "Q10") (pin "6") (pinfunction "P-D_6") (pintype "passive"))
      (node (ref "Q10") (pin "7") (pinfunction "P-D_7") (pintype "passive"))
      (node (ref "Q10") (pin "8") (pinfunction "P-D_8") (pintype "passive"))
    )
    (net (code "57") (name "Net-(A-PadC)") (class "Default")
      (node (ref "A") (pin "C") (pinfunction "C_C") (pintype "passive"))
      (node (ref "R37") (pin "1") (pinfunction "1_1") (pintype "passive"))
    )
    (net (code "58") (name "Net-(B-PadC)") (class "Default")
      (node (ref "B") (pin "C") (pinfunction "C_C") (pintype "passive"))
      (node (ref "R38") (pin "1") (pinfunction "1_1") (pintype "passive"))
    )
    (net (code "59") (name "Net-(BUZZ-Pad2)") (class "Default")
      (node (ref "BUZZ") (pin "2") (pinfunction "2_2") (pintype "passive"))
      (node (ref "D11") (pin "C") (pinfunction "C_C") (pintype "passive"))
      (node (ref "T1") (pin "C") (pinfunction "C_C") (pintype "passive"))
    )
    (net (code "60") (name "Net-(IC1-HIN1)") (class "Default")
      (node (ref "IC1") (pin "1") (pinfunction "HIN1_1") (pintype "input"))
      (node (ref "IC4") (pin "7") (pinfunction "Y_7") (pintype "output"))
    )
    (net (code "61") (name "Net-(IC1-HIN2)") (class "Default")
      (node (ref "IC1") (pin "3") (pinfunction "HIN2_3") (pintype "input"))
      (node (ref "IC4") (pin "5") (pinfunction "Y_5") (pintype "output"))
    )
    (net (code "62") (name "Net-(IC1-HIN3)") (class "Default")
      (node (ref "IC1") (pin "5") (pinfunction "HIN3_5") (pintype "input"))
      (node (ref "IC4") (pin "2") (pinfunction "Y_2") (pintype "output"))
    )
    (net (code "63") (name "Net-(IC1-HO1)") (class "Default")
      (node (ref "IC1") (pin "19") (pinfunction "HO1_19") (pintype "output"))
      (node (ref "R5") (pin "1") (pinfunction "1_1") (pintype "passive"))
    )
    (net (code "64") (name "Net-(IC1-HO2)") (class "Default")
      (node (ref "IC1") (pin "15") (pinfunction "HO2_15") (pintype "output"))
      (node (ref "R3") (pin "1") (pinfunction "1_1") (pintype "passive"))
    )
    (net (code "65") (name "Net-(IC1-HO3)") (class "Default")
      (node (ref "IC1") (pin "9") (pinfunction "HO3_9") (pintype "output"))
      (node (ref "R1") (pin "1") (pinfunction "1_1") (pintype "passive"))
    )
    (net (code "66") (name "Net-(IC1-LO1)") (class "Default")
      (node (ref "IC1") (pin "17") (pinfunction "LO1_17") (pintype "output"))
      (node (ref "R6") (pin "1") (pinfunction "1_1") (pintype "passive"))
    )
    (net (code "67") (name "Net-(IC1-LO2)") (class "Default")
      (node (ref "IC1") (pin "13") (pinfunction "LO2_13") (pintype "output"))
      (node (ref "R4") (pin "1") (pinfunction "1_1") (pintype "passive"))
    )
    (net (code "68") (name "Net-(IC1-LO3)") (class "Default")
      (node (ref "IC1") (pin "7") (pinfunction "LO3_7") (pintype "output"))
      (node (ref "R2") (pin "1") (pinfunction "1_1") (pintype "passive"))
    )
    (net (code "69") (name "Net-(IC1-VB1)") (class "Default")
      (node (ref "C1") (pin "1") (pinfunction "1_1") (pintype "passive"))
      (node (ref "D1") (pin "C") (pinfunction "C_C") (pintype "passive"))
      (node (ref "IC1") (pin "20") (pinfunction "VB1_20") (pintype "input"))
    )
    (net (code "70") (name "Net-(IC1-VB2)") (class "Default")
      (node (ref "C2") (pin "1") (pinfunction "1_1") (pintype "passive"))
      (node (ref "D2") (pin "C") (pinfunction "C_C") (pintype "passive"))
      (node (ref "IC1") (pin "16") (pinfunction "VB2_16") (pintype "input"))
    )
    (net (code "71") (name "Net-(IC1-VB3)") (class "Default")
      (node (ref "C3") (pin "1") (pinfunction "1_1") (pintype "passive"))
      (node (ref "D3") (pin "C") (pinfunction "C_C") (pintype "passive"))
      (node (ref "IC1") (pin "10") (pinfunction "VB3_10") (pintype "input"))
    )
    (net (code "72") (name "Net-(IC2-HIN1)") (class "Default")
      (node (ref "IC2") (pin "1") (pinfunction "HIN1_1") (pintype "input"))
      (node (ref "IC5") (pin "7") (pinfunction "Y_7") (pintype "output"))
    )
    (net (code "73") (name "Net-(IC2-HIN2)") (class "Default")
      (node (ref "IC2") (pin "3") (pinfunction "HIN2_3") (pintype "input"))
      (node (ref "IC5") (pin "5") (pinfunction "Y_5") (pintype "output"))
    )
    (net (code "74") (name "Net-(IC2-HIN3)") (class "Default")
      (node (ref "IC2") (pin "5") (pinfunction "HIN3_5") (pintype "input"))
      (node (ref "IC5") (pin "2") (pinfunction "Y_2") (pintype "output"))
    )
    (net (code "75") (name "Net-(IC2-HO1)") (class "Default")
      (node (ref "IC2") (pin "19") (pinfunction "HO1_19") (pintype "output"))
      (node (ref "R11") (pin "1") (pinfunction "1_1") (pintype "passive"))
    )
    (net (code "76") (name "Net-(IC2-HO2)") (class "Default")
      (node (ref "IC2") (pin "15") (pinfunction "HO2_15") (pintype "output"))
      (node (ref "R9") (pin "1") (pinfunction "1_1") (pintype "passive"))
    )
    (net (code "77") (name "Net-(IC2-HO3)") (class "Default")
      (node (ref "IC2") (pin "9") (pinfunction "HO3_9") (pintype "output"))
      (node (ref "R7") (pin "1") (pinfunction "1_1") (pintype "passive"))
    )
    (net (code "78") (name "Net-(IC2-LO1)") (class "Default")
      (node (ref "IC2") (pin "17") (pinfunction "LO1_17") (pintype "output"))
      (node (ref "R12") (pin "1") (pinfunction "1_1") (pintype "passive"))
    )
    (net (code "79") (name "Net-(IC2-LO2)") (class "Default")
      (node (ref "IC2") (pin "13") (pinfunction "LO2_13") (pintype "output"))
      (node (ref "R10") (pin "1") (pinfunction "1_1") (pintype "passive"))
    )
    (net (code "80") (name "Net-(IC2-LO3)") (class "Default")
      (node (ref "IC2") (pin "7") (pinfunction "LO3_7") (pintype "output"))
      (node (ref "R8") (pin "1") (pinfunction "1_1") (pintype "passive"))
    )
    (net (code "81") (name "Net-(IC2-VB1)") (class "Default")
      (node (ref "C5") (pin "1") (pinfunction "1_1") (pintype "passive"))
      (node (ref "D4") (pin "C") (pinfunction "C_C") (pintype "passive"))
      (node (ref "IC2") (pin "20") (pinfunction "VB1_20") (pintype "input"))
    )
    (net (code "82") (name "Net-(IC2-VB2)") (class "Default")
      (node (ref "C6") (pin "1") (pinfunction "1_1") (pintype "passive"))
      (node (ref "D5") (pin "C") (pinfunction "C_C") (pintype "passive"))
      (node (ref "IC2") (pin "16") (pinfunction "VB2_16") (pintype "input"))
    )
    (net (code "83") (name "Net-(IC2-VB3)") (class "Default")
      (node (ref "C7") (pin "1") (pinfunction "1_1") (pintype "passive"))
      (node (ref "D6") (pin "C") (pinfunction "C_C") (pintype "passive"))
      (node (ref "IC2") (pin "10") (pinfunction "VB3_10") (pintype "input"))
    )
    (net (code "84") (name "Net-(IC3-HIN1)") (class "Default")
      (node (ref "IC3") (pin "1") (pinfunction "HIN1_1") (pintype "input"))
      (node (ref "IC6") (pin "7") (pinfunction "Y_7") (pintype "output"))
    )
    (net (code "85") (name "Net-(IC3-HIN2)") (class "Default")
      (node (ref "IC3") (pin "3") (pinfunction "HIN2_3") (pintype "input"))
      (node (ref "IC6") (pin "5") (pinfunction "Y_5") (pintype "output"))
    )
    (net (code "86") (name "Net-(IC3-HIN3)") (class "Default")
      (node (ref "IC3") (pin "5") (pinfunction "HIN3_5") (pintype "input"))
      (node (ref "IC6") (pin "2") (pinfunction "Y_2") (pintype "output"))
    )
    (net (code "87") (name "Net-(IC3-HO1)") (class "Default")
      (node (ref "IC3") (pin "19") (pinfunction "HO1_19") (pintype "output"))
      (node (ref "R17") (pin "1") (pinfunction "1_1") (pintype "passive"))
    )
    (net (code "88") (name "Net-(IC3-HO2)") (class "Default")
      (node (ref "IC3") (pin "15") (pinfunction "HO2_15") (pintype "output"))
      (node (ref "R15") (pin "1") (pinfunction "1_1") (pintype "passive"))
    )
    (net (code "89") (name "Net-(IC3-HO3)") (class "Default")
      (node (ref "IC3") (pin "9") (pinfunction "HO3_9") (pintype "output"))
      (node (ref "R13") (pin "1") (pinfunction "1_1") (pintype "passive"))
    )
    (net (code "90") (name "Net-(IC3-LO1)") (class "Default")
      (node (ref "IC3") (pin "17") (pinfunction "LO1_17") (pintype "output"))
      (node (ref "R18") (pin "1") (pinfunction "1_1") (pintype "passive"))
    )
    (net (code "91") (name "Net-(IC3-LO2)") (class "Default")
      (node (ref "IC3") (pin "13") (pinfunction "LO2_13") (pintype "output"))
      (node (ref "R16") (pin "1") (pinfunction "1_1") (pintype "passive"))
    )
    (net (code "92") (name "Net-(IC3-LO3)") (class "Default")
      (node (ref "IC3") (pin "7") (pinfunction "LO3_7") (pintype "output"))
      (node (ref "R14") (pin "1") (pinfunction "1_1") (pintype "passive"))
    )
    (net (code "93") (name "Net-(IC3-VB1)") (class "Default")
      (node (ref "C9") (pin "1") (pinfunction "1_1") (pintype "passive"))
      (node (ref "D7") (pin "C") (pinfunction "C_C") (pintype "passive"))
      (node (ref "IC3") (pin "20") (pinfunction "VB1_20") (pintype "input"))
    )
    (net (code "94") (name "Net-(IC3-VB2)") (class "Default")
      (node (ref "C10") (pin "1") (pinfunction "1_1") (pintype "passive"))
      (node (ref "D8") (pin "C") (pinfunction "C_C") (pintype "passive"))
      (node (ref "IC3") (pin "16") (pinfunction "VB2_16") (pintype "input"))
    )
    (net (code "95") (name "Net-(IC3-VB3)") (class "Default")
      (node (ref "C11") (pin "1") (pinfunction "1_1") (pintype "passive"))
      (node (ref "D9") (pin "C") (pinfunction "C_C") (pintype "passive"))
      (node (ref "IC3") (pin "10") (pinfunction "VB3_10") (pintype "input"))
    )
    (net (code "96") (name "Net-(IC9-NR)") (class "Default")
      (node (ref "C36") (pin "1") (pinfunction "1_1") (pintype "passive"))
      (node (ref "IC9") (pin "4") (pinfunction "NR_4") (pintype "passive"))
    )
    (net (code "97") (name "Net-(IC10-NR)") (class "Default")
      (node (ref "C40") (pin "1") (pinfunction "1_1") (pintype "passive"))
      (node (ref "IC10") (pin "4") (pinfunction "NR_4") (pintype "passive"))
    )
    (net (code "98") (name "Net-(IC11-CAP+)") (class "Default")
      (node (ref "C28") (pin "1") (pinfunction "1_1") (pintype "passive"))
      (node (ref "IC11") (pin "6") (pinfunction "CAP+_6") (pintype "passive"))
    )
    (net (code "99") (name "Net-(IC11-CAP-)") (class "Default")
      (node (ref "C28") (pin "2") (pinfunction "2_2") (pintype "passive"))
      (node (ref "IC11") (pin "3") (pinfunction "CAP-_3") (pintype "passive"))
    )
    (net (code "100") (name "Net-(IN1-Pad1)") (class "Default")
      (node (ref "IN1") (pin "1") (pinfunction "1_1") (pintype "passive"))
      (node (ref "R22") (pin "2") (pinfunction "2_2") (pintype "passive"))
    )
    (net (code "101") (name "Net-(IN2-Pad1)") (class "Default")
      (node (ref "IN2") (pin "1") (pinfunction "1_1") (pintype "passive"))
      (node (ref "R21") (pin "2") (pinfunction "2_2") (pintype "passive"))
    )
    (net (code "102") (name "Net-(IN3-Pad1)") (class "Default")
      (node (ref "IN3") (pin "1") (pinfunction "1_1") (pintype "passive"))
      (node (ref "R20") (pin "2") (pinfunction "2_2") (pintype "passive"))
    )
    (net (code "103") (name "Net-(IN4-Pad1)") (class "Default")
      (node (ref "IN4") (pin "1") (pinfunction "1_1") (pintype "passive"))
      (node (ref "R19") (pin "2") (pinfunction "2_2") (pintype "passive"))
    )
    (net (code "104") (name "Net-(L1-Pad2)") (class "Default")
      (node (ref "L1") (pin "2") (pinfunction "2_2") (pintype "passive"))
      (node (ref "USB") (pin "1") (pinfunction "1_1") (pintype "passive"))
    )
    (net (code "105") (name "Net-(ON-PadC)") (class "Default")
      (node (ref "ON") (pin "C") (pinfunction "C_C") (pintype "passive"))
      (node (ref "R36") (pin "1") (pinfunction "1_1") (pintype "passive"))
    )
    (net (code "106") (name "Net-(PWR-PadC)") (class "Default")
      (node (ref "PWR") (pin "C") (pinfunction "C_C") (pintype "passive"))
      (node (ref "R35") (pin "1") (pinfunction "1_1") (pintype "passive"))
    )
    (net (code "107") (name "Net-(Q1A-N-G)") (class "Default")
      (node (ref "Q1") (pin "4") (pinfunction "N-G_4") (pintype "passive"))
      (node (ref "R1") (pin "2") (pinfunction "2_2") (pintype "passive"))
    )
    (net (code "108") (name "Net-(Q1B-N-G)") (class "Default")
      (node (ref "Q1") (pin "2") (pinfunction "N-G_2") (pintype "passive"))
      (node (ref "R2") (pin "2") (pinfunction "2_2") (pintype "passive"))
    )
    (net (code "109") (name "Net-(Q2A-N-G)") (class "Default")
      (node (ref "Q2") (pin "4") (pinfunction "N-G_4") (pintype "passive"))
      (node (ref "R3") (pin "2") (pinfunction "2_2") (pintype "passive"))
    )
    (net (code "110") (name "Net-(Q2B-N-G)") (class "Default")
      (node (ref "Q2") (pin "2") (pinfunction "N-G_2") (pintype "passive"))
      (node (ref "R4") (pin "2") (pinfunction "2_2") (pintype "passive"))
    )
    (net (code "111") (name "Net-(Q3A-N-G)") (class "Default")
      (node (ref "Q3") (pin "4") (pinfunction "N-G_4") (pintype "passive"))
      (node (ref "R5") (pin "2") (pinfunction "2_2") (pintype "passive"))
    )
    (net (code "112") (name "Net-(Q3B-N-G)") (class "Default")
      (node (ref "Q3") (pin "2") (pinfunction "N-G_2") (pintype "passive"))
      (node (ref "R6") (pin "2") (pinfunction "2_2") (pintype "passive"))
    )
    (net (code "113") (name "Net-(Q4A-N-G)") (class "Default")
      (node (ref "Q4") (pin "4") (pinfunction "N-G_4") (pintype "passive"))
      (node (ref "R7") (pin "2") (pinfunction "2_2") (pintype "passive"))
    )
    (net (code "114") (name "Net-(Q4B-N-G)") (class "Default")
      (node (ref "Q4") (pin "2") (pinfunction "N-G_2") (pintype "passive"))
      (node (ref "R8") (pin "2") (pinfunction "2_2") (pintype "passive"))
    )
    (net (code "115") (name "Net-(Q5A-N-G)") (class "Default")
      (node (ref "Q5") (pin "4") (pinfunction "N-G_4") (pintype "passive"))
      (node (ref "R9") (pin "2") (pinfunction "2_2") (pintype "passive"))
    )
    (net (code "116") (name "Net-(Q5B-N-G)") (class "Default")
      (node (ref "Q5") (pin "2") (pinfunction "N-G_2") (pintype "passive"))
      (node (ref "R10") (pin "2") (pinfunction "2_2") (pintype "passive"))
    )
    (net (code "117") (name "Net-(Q6A-N-G)") (class "Default")
      (node (ref "Q6") (pin "4") (pinfunction "N-G_4") (pintype "passive"))
      (node (ref "R11") (pin "2") (pinfunction "2_2") (pintype "passive"))
    )
    (net (code "118") (name "Net-(Q6B-N-G)") (class "Default")
      (node (ref "Q6") (pin "2") (pinfunction "N-G_2") (pintype "passive"))
      (node (ref "R12") (pin "2") (pinfunction "2_2") (pintype "passive"))
    )
    (net (code "119") (name "Net-(Q7A-N-G)") (class "Default")
      (node (ref "Q7") (pin "4") (pinfunction "N-G_4") (pintype "passive"))
      (node (ref "R13") (pin "2") (pinfunction "2_2") (pintype "passive"))
    )
    (net (code "120") (name "Net-(Q7B-N-G)") (class "Default")
      (node (ref "Q7") (pin "2") (pinfunction "N-G_2") (pintype "passive"))
      (node (ref "R14") (pin "2") (pinfunction "2_2") (pintype "passive"))
    )
    (net (code "121") (name "Net-(Q8A-N-G)") (class "Default")
      (node (ref "Q8") (pin "4") (pinfunction "N-G_4") (pintype "passive"))
      (node (ref "R15") (pin "2") (pinfunction "2_2") (pintype "passive"))
    )
    (net (code "122") (name "Net-(Q8B-N-G)") (class "Default")
      (node (ref "Q8") (pin "2") (pinfunction "N-G_2") (pintype "passive"))
      (node (ref "R16") (pin "2") (pinfunction "2_2") (pintype "passive"))
    )
    (net (code "123") (name "Net-(Q9A-N-G)") (class "Default")
      (node (ref "Q9") (pin "4") (pinfunction "N-G_4") (pintype "passive"))
      (node (ref "R17") (pin "2") (pinfunction "2_2") (pintype "passive"))
    )
    (net (code "124") (name "Net-(Q9B-N-G)") (class "Default")
      (node (ref "Q9") (pin "2") (pinfunction "N-G_2") (pintype "passive"))
      (node (ref "R18") (pin "2") (pinfunction "2_2") (pintype "passive"))
    )
    (net (code "125") (name "Net-(R23-Pad2)") (class "Default")
      (node (ref "R23") (pin "2") (pinfunction "2_2") (pintype "passive"))
      (node (ref "USB") (pin "2") (pinfunction "2_2") (pintype "passive"))
    )
    (net (code "126") (name "Net-(R24-Pad2)") (class "Default")
      (node (ref "R24") (pin "2") (pinfunction "2_2") (pintype "passive"))
      (node (ref "USB") (pin "3") (pinfunction "3_3") (pintype "passive"))
    )
    (net (code "127") (name "Net-(R39-Pad2)") (class "Default")
      (node (ref "R39") (pin "2") (pinfunction "2_2") (pintype "passive"))
      (node (ref "R40") (pin "1") (pinfunction "1_1") (pintype "passive"))
      (node (ref "T1") (pin "B") (pinfunction "B_B") (pintype "passive"))
    )
    (net (code "128") (name "Net-(RX-P)") (class "Default")
      (node (ref "R28") (pin "1") (pinfunction "1_1") (pintype "passive"))
      (node (ref "RX") (pin "PAD") (pinfunction "P_PAD") (pintype "passive"))
    )
    (net (code "129") (name "Net-(TX-P)") (class "Default")
      (node (ref "R29") (pin "1") (pinfunction "1_1") (pintype "passive"))
      (node (ref "TX") (pin "PAD") (pinfunction "P_PAD") (pintype "passive"))
    )
    (net (code "130") (name "VCC") (class "Default")
      (node (ref "C13") (pin "+") (pinfunction "+_+") (pintype "passive"))
      (node (ref "C14") (pin "+") (pinfunction "+_+") (pintype "passive"))
      (node (ref "C15") (pin "1") (pinfunction "1_1") (pintype "passive"))
      (node (ref "C16") (pin "1") (pinfunction "1_1") (pintype "passive"))
      (node (ref "C32") (pin "+") (pinfunction "+_+") (pintype "passive"))
      (node (ref "C33") (pin "1") (pinfunction "1_1") (pintype "passive"))
      (node (ref "IC8") (pin "1") (pinfunction "VI_1") (pintype "input"))
      (node (ref "Q1") (pin "5") (pinfunction "N-D_5") (pintype "passive"))
      (node (ref "Q1") (pin "6") (pinfunction "N-D_6") (pintype "passive"))
      (node (ref "Q10") (pin "1") (pinfunction "P-S_1") (pintype "passive"))
      (node (ref "Q10") (pin "2") (pinfunction "P-S_2") (pintype "passive"))
      (node (ref "Q10") (pin "3") (pinfunction "P-S_3") (pintype "passive"))
      (node (ref "Q2") (pin "5") (pinfunction "N-D_5") (pintype "passive"))
      (node (ref "Q2") (pin "6") (pinfunction "N-D_6") (pintype "passive"))
      (node (ref "Q3") (pin "5") (pinfunction "N-D_5") (pintype "passive"))
      (node (ref "Q3") (pin "6") (pinfunction "N-D_6") (pintype "passive"))
      (node (ref "Q4") (pin "5") (pinfunction "N-D_5") (pintype "passive"))
      (node (ref "Q4") (pin "6") (pinfunction "N-D_6") (pintype "passive"))
      (node (ref "Q5") (pin "5") (pinfunction "N-D_5") (pintype "passive"))
      (node (ref "Q5") (pin "6") (pinfunction "N-D_6") (pintype "passive"))
      (node (ref "Q6") (pin "5") (pinfunction "N-D_5") (pintype "passive"))
      (node (ref "Q6") (pin "6") (pinfunction "N-D_6") (pintype "passive"))
      (node (ref "Q7") (pin "5") (pinfunction "N-D_5") (pintype "passive"))
      (node (ref "Q7") (pin "6") (pinfunction "N-D_6") (pintype "passive"))
      (node (ref "Q8") (pin "5") (pinfunction "N-D_5") (pintype "passive"))
      (node (ref "Q8") (pin "6") (pinfunction "N-D_6") (pintype "passive"))
      (node (ref "Q9") (pin "5") (pinfunction "N-D_5") (pintype "passive"))
      (node (ref "Q9") (pin "6") (pinfunction "N-D_6") (pintype "passive"))
      (node (ref "R32") (pin "1") (pinfunction "1_1") (pintype "passive"))
    )
    (net (code "131") (name "unconnected-(USB-Pad4)") (class "Default")
      (node (ref "USB") (pin "4") (pinfunction "4_4") (pintype "passive"))
    )
  )
)
